# CV_Control.net
KiCad netlist of a schematic drawn in Altium Designer
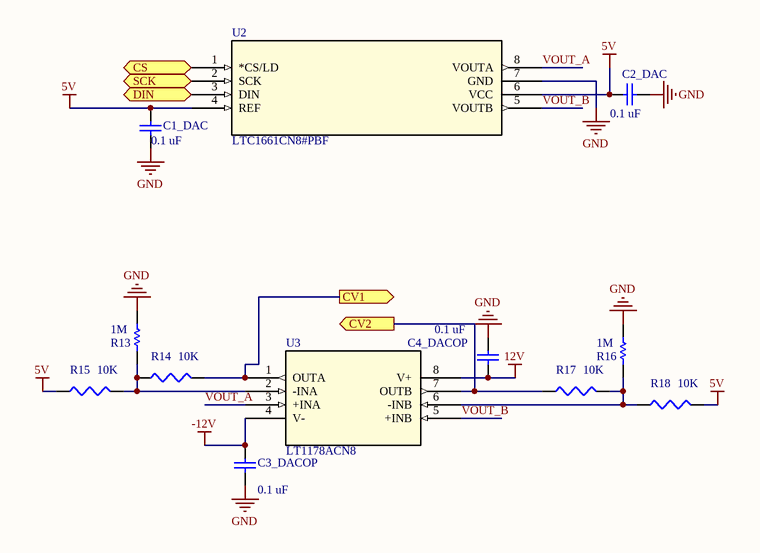
[diagram p0: CV_Control.SchDoc]

(export (version "E")
  (design (tool "Eeschema 10.0.6"))
  (components
    (comp (ref "C1_DAC")
      (value "0.1 uF")
      (footprint "C0805")
      (description "Capacitor")
      (fields (field (name "PUBLISHER") "Altium Limited"))
      (libsource (lib "Miscellaneous Devices") (part "Cap"))
    )
    (comp (ref "C2_DAC")
      (value "0.1 uF")
      (footprint "C0805")
      (description "Capacitor")
      (fields (field (name "PUBLISHER") "Altium Limited"))
      (libsource (lib "Miscellaneous Devices") (part "Cap"))
    )
    (comp (ref "C3_DACOP")
      (value "0.1 uF")
      (footprint "C0805")
      (description "Capacitor")
      (fields (field (name "PUBLISHER") "Altium Limited"))
      (libsource (lib "Miscellaneous Devices") (part "Cap"))
    )
    (comp (ref "C4_DACOP")
      (value "0.1 uF")
      (footprint "C0805")
      (description "Capacitor")
      (fields (field (name "PUBLISHER") "Altium Limited"))
      (libsource (lib "Miscellaneous Devices") (part "Cap"))
    )
    (comp (ref "R13")
      (value "1M")
      (footprint "AXIAL-0.3")
      (description "Resistor")
      (fields (field (name "Comment") "Res1") (field (name "PUBLISHER") "Altium Limited"))
      (libsource (lib "Miscellaneous Devices") (part "Res1"))
    )
    (comp (ref "R14")
      (value "10K")
      (footprint "J1-0603")
      (description "Resistor")
      (fields (field (name "Comment") "Res3") (field (name "PUBLISHER") "Altium Limited"))
      (libsource (lib "Miscellaneous Devices") (part "Res3"))
    )
    (comp (ref "R15")
      (value "10K")
      (footprint "J1-0603")
      (description "Resistor")
      (fields (field (name "Comment") "Res3") (field (name "PUBLISHER") "Altium Limited"))
      (libsource (lib "Miscellaneous Devices") (part "Res3"))
    )
    (comp (ref "R16")
      (value "1M")
      (footprint "AXIAL-0.3")
      (description "Resistor")
      (fields (field (name "Comment") "Res1") (field (name "PUBLISHER") "Altium Limited"))
      (libsource (lib "Miscellaneous Devices") (part "Res1"))
    )
    (comp (ref "R17")
      (value "10K")
      (footprint "J1-0603")
      (description "Resistor")
      (fields (field (name "Comment") "Res3") (field (name "PUBLISHER") "Altium Limited"))
      (libsource (lib "Miscellaneous Devices") (part "Res3"))
    )
    (comp (ref "R18")
      (value "10K")
      (footprint "J1-0603")
      (description "Resistor")
      (fields (field (name "Comment") "Res3") (field (name "PUBLISHER") "Altium Limited"))
      (libsource (lib "Miscellaneous Devices") (part "Res3"))
    )
    (comp (ref "U2")
      (value "LTC1661CN8#PBF")
      (footprint "PDIP-8_N")
      (description "Imported")
      (libsource (lib "lt1661") (part "LTC1661CN8#PBF"))
    )
    (comp (ref "U3")
      (value "LT1178ACN8")
      (footprint "PDIP-8_N")
      (description "Imported")
      (fields
        (field (name "MANUFACTURER_PART_NUMBER") "LT1632CN8#PBF")
        (field (name "DIGIKEYPARTNUMBER") "LT1632CN8-ND")
        (field (name "COPYRIGHT") "Copyright (C) 2015 Accelerated Designs. All rights reserved")
      )
      (libsource (lib "lt1632") (part "LT1632CN8#PBF"))
    )
  )
  (nets
    (net (code "1") (name "-12V") (class "Default")
      (node (ref "C3_DACOP") (pin "1") (pinfunction "1_1") (pintype "passive"))
      (node (ref "U3") (pin "4") (pinfunction "V-_4") (pintype "power_in"))
    )
    (net (code "2") (name "/CS") (class "Default")
      (node (ref "U2") (pin "1") (pinfunction "*CS/LD_1") (pintype "input"))
    )
    (net (code "3") (name "/CV1") (class "Default")
      (node (ref "R14") (pin "2") (pinfunction "2_2") (pintype "passive"))
      (node (ref "U3") (pin "1") (pinfunction "OUTA_1") (pintype "output"))
    )
    (net (code "4") (name "/CV2") (class "Default")
      (node (ref "R17") (pin "1") (pinfunction "1_1") (pintype "passive"))
      (node (ref "U3") (pin "7") (pinfunction "OUTB_7") (pintype "output"))
    )
    (net (code "5") (name "/DIN") (class "Default")
      (node (ref "U2") (pin "3") (pinfunction "DIN_3") (pintype "input"))
    )
    (net (code "6") (name "/SCK") (class "Default")
      (node (ref "U2") (pin "2") (pinfunction "SCK_2") (pintype "input"))
    )
    (net (code "7") (name "/VOUT_A") (class "Default")
      (node (ref "U2") (pin "8") (pinfunction "VOUTA_8") (pintype "output"))
      (node (ref "U3") (pin "3") (pinfunction "+INA_3") (pintype "input"))
    )
    (net (code "8") (name "/VOUT_B") (class "Default")
      (node (ref "U2") (pin "5") (pinfunction "VOUTB_5") (pintype "output"))
      (node (ref "U3") (pin "5") (pinfunction "+INB_5") (pintype "input"))
    )
    (net (code "9") (name "5V") (class "Default")
      (node (ref "C1_DAC") (pin "2") (pinfunction "2_2") (pintype "passive"))
      (node (ref "C2_DAC") (pin "1") (pinfunction "1_1") (pintype "passive"))
      (node (ref "R15") (pin "1") (pinfunction "1_1") (pintype "passive"))
      (node (ref "R18") (pin "2") (pinfunction "2_2") (pintype "passive"))
      (node (ref "U2") (pin "4") (pinfunction "REF_4") (pintype "input"))
      (node (ref "U2") (pin "6") (pinfunction "VCC_6") (pintype "power_in"))
    )
    (net (code "10") (name "12V") (class "Default")
      (node (ref "C4_DACOP") (pin "1") (pinfunction "1_1") (pintype "passive"))
      (node (ref "U3") (pin "8") (pinfunction "V+_8") (pintype "power_in"))
    )
    (net (code "11") (name "GND") (class "Default")
      (node (ref "C1_DAC") (pin "1") (pinfunction "1_1") (pintype "passive"))
      (node (ref "C2_DAC") (pin "2") (pinfunction "2_2") (pintype "passive"))
      (node (ref "C3_DACOP") (pin "2") (pinfunction "2_2") (pintype "passive"))
      (node (ref "C4_DACOP") (pin "2") (pinfunction "2_2") (pintype "passive"))
      (node (ref "R13") (pin "2") (pinfunction "2_2") (pintype "passive"))
      (node (ref "R16") (pin "2") (pinfunction "2_2") (pintype "passive"))
      (node (ref "U2") (pin "7") (pinfunction "GND_7") (pintype "power_in"))
    )
    (net (code "12") (name "Net-(U3--INA)") (class "Default")
      (node (ref "R13") (pin "1") (pinfunction "1_1") (pintype "passive"))
      (node (ref "R14") (pin "1") (pinfunction "1_1") (pintype "passive"))
      (node (ref "R15") (pin "2") (pinfunction "2_2") (pintype "passive"))
      (node (ref "U3") (pin "2") (pinfunction "-INA_2") (pintype "input"))
    )
    (net (code "13") (name "Net-(U3--INB)") (class "Default")
      (node (ref "R16") (pin "1") (pinfunction "1_1") (pintype "passive"))
      (node (ref "R17") (pin "2") (pinfunction "2_2") (pintype "passive"))
      (node (ref "R18") (pin "1") (pinfunction "1_1") (pintype "passive"))
      (node (ref "U3") (pin "6") (pinfunction "-INB_6") (pintype "input"))
    )
  )
)
